# ANYA_2620_V1_I1.net
KiCad netlist of a schematic drawn in Altium Designer
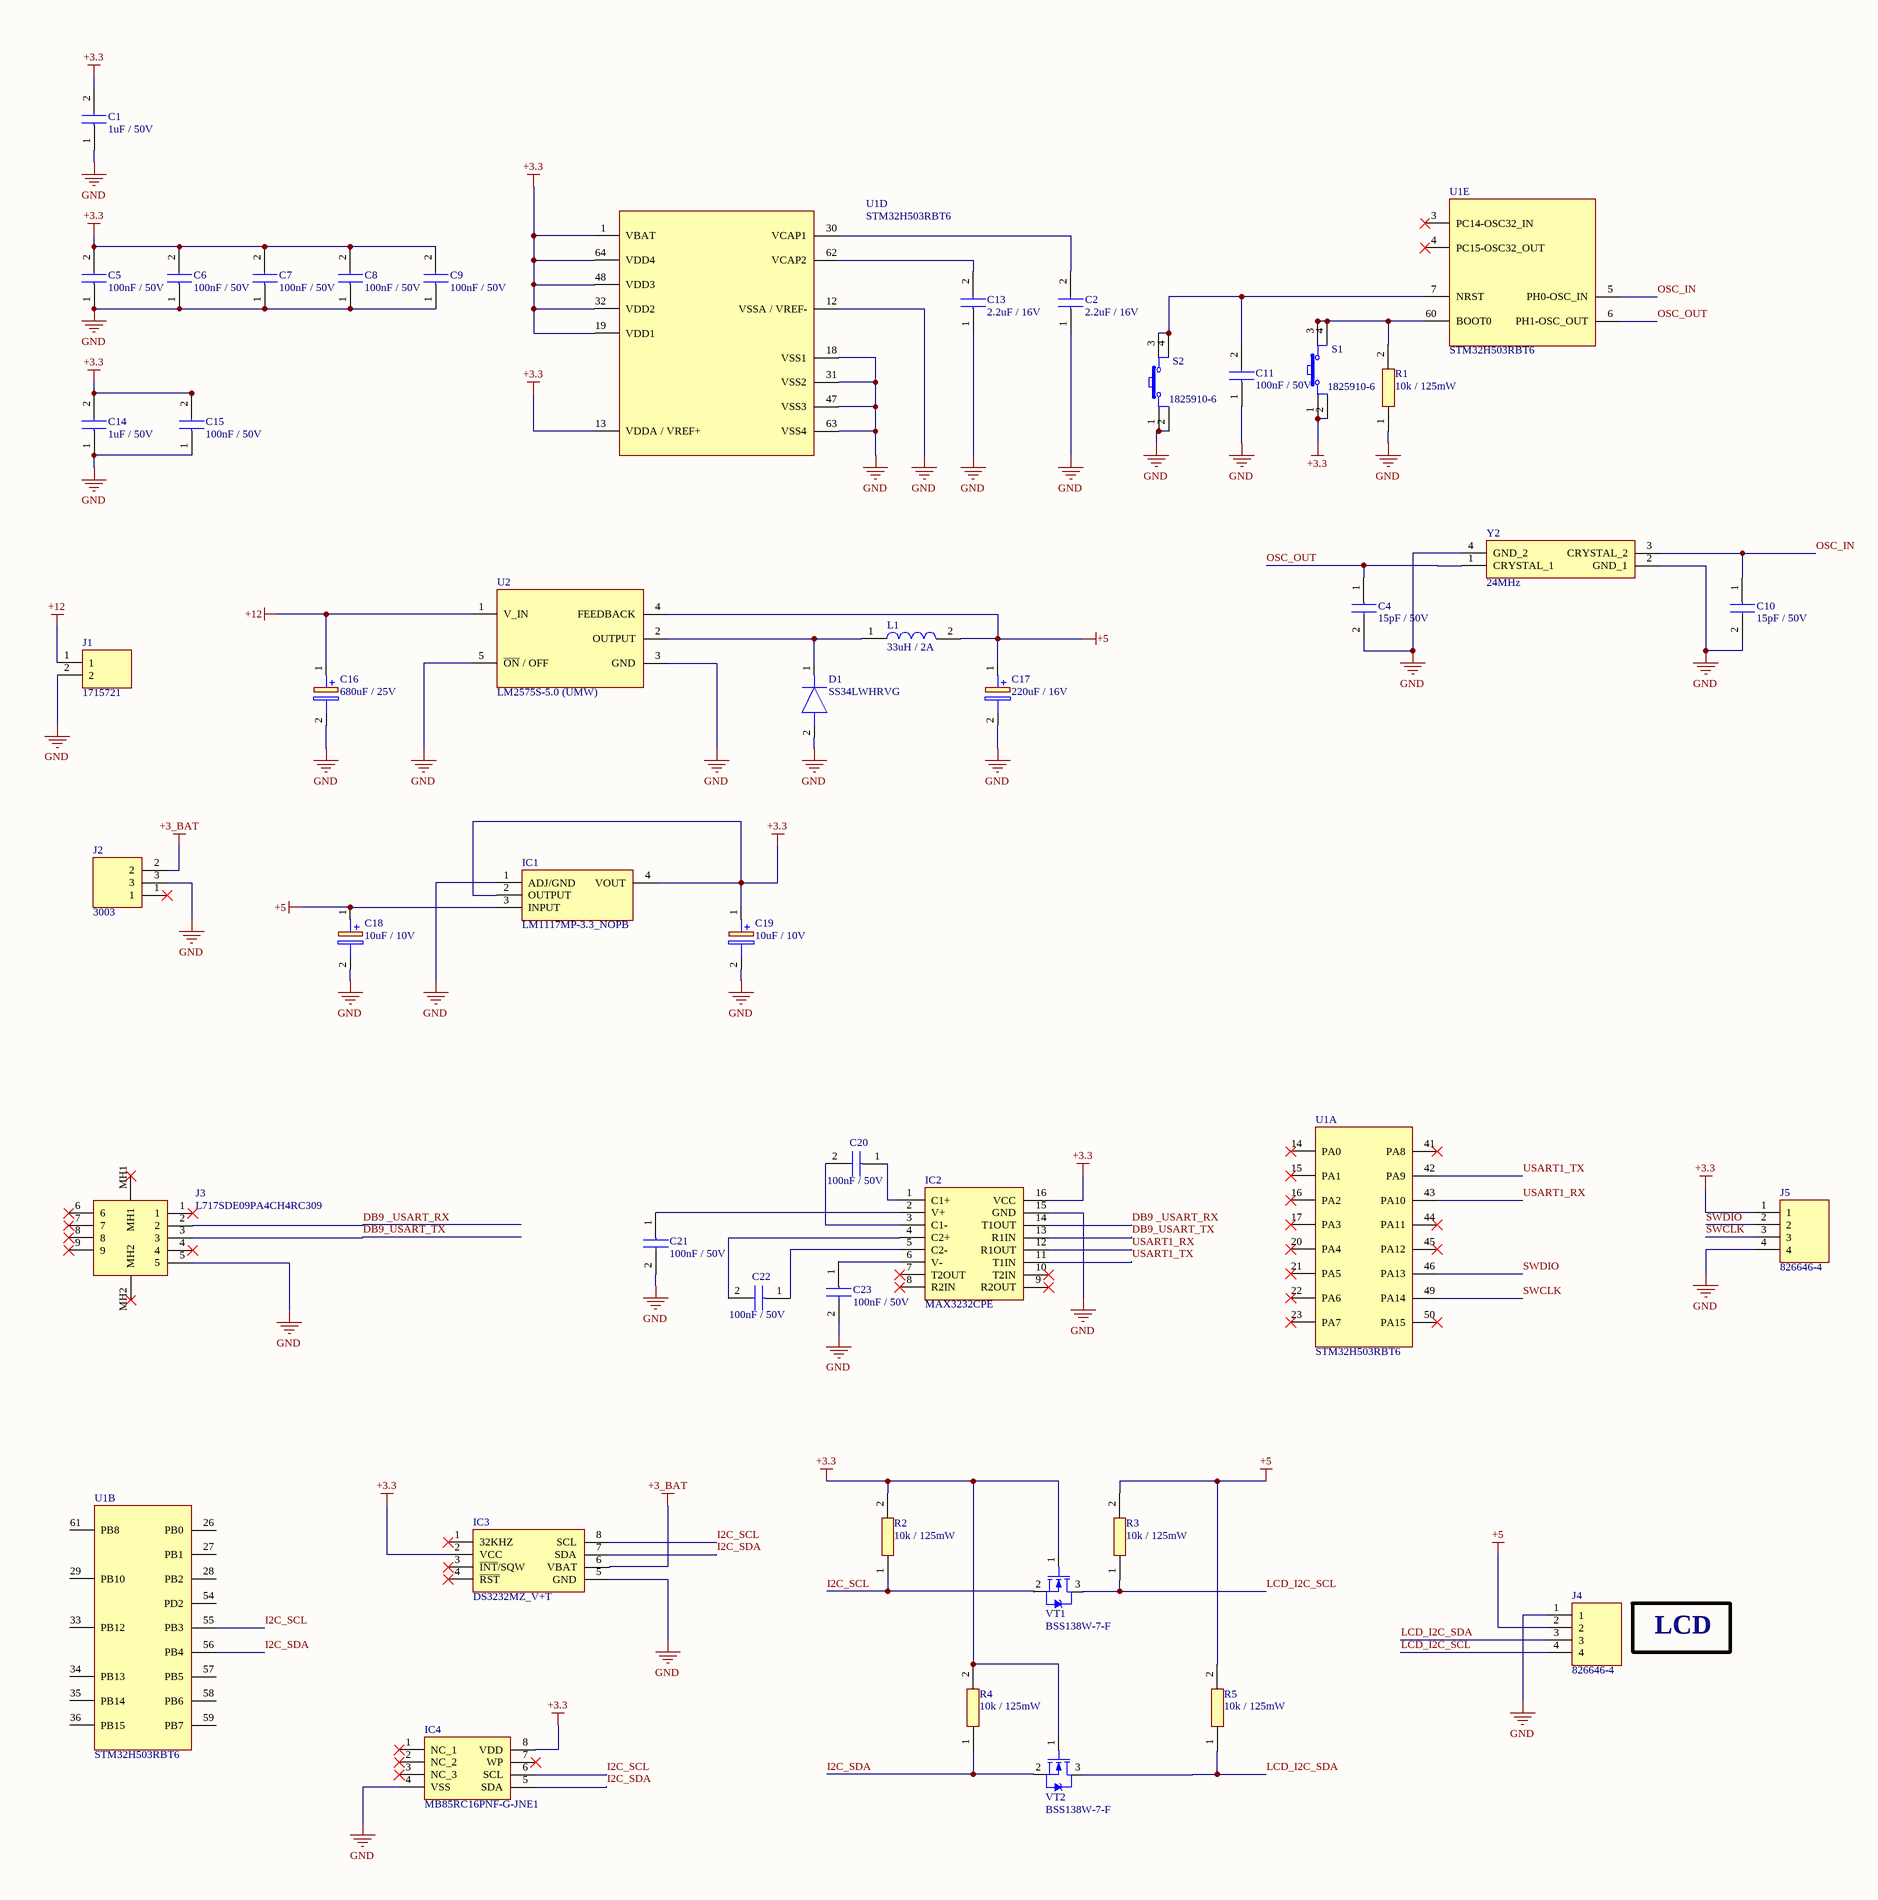
[diagram p0: ANYA_2620_V1_I1.SchDoc, left]
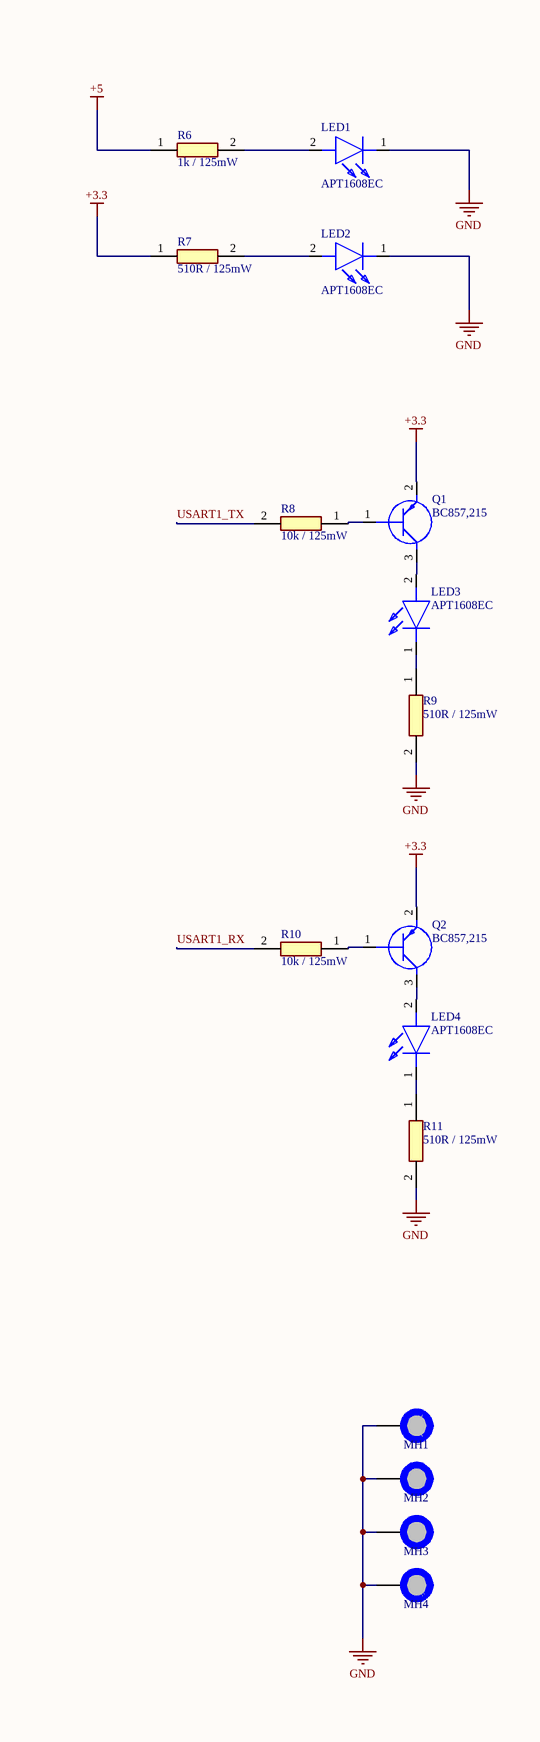
[diagram p1: ANYA_2620_V1_I1.SchDoc, right]

(export (version "E")
  (design (tool "Eeschema 10.0.6"))
  (components
    (comp (ref "C1")
      (value "1uF / 50V")
      (footprint "SamacSys:CAPC2012X145N")
      (description "Capacitor")
      (fields
        (field (name "MANUFACTURER_PART_NUMBER") "GRM21BR71H105KA12L")
        (field (name "MOUSER PART NUMBER") "81-GRM21BR71H105KA2L")
      )
      (libsource (lib "*") (part "GRM21BR71H105KA12L"))
    )
    (comp (ref "C2")
      (value "2.2uF / 16V")
      (footprint "SamacSys:CAPC2012X145N")
      (description "Capacitor")
      (fields
        (field (name "MANUFACTURER_PART_NUMBER") "GRM21BR71C225KA12L")
        (field (name "MOUSER PART NUMBER") "81-GRM21BR71C225KA2L")
      )
      (libsource (lib "*") (part "GRM21BR71C225KA12L"))
    )
    (comp (ref "C4")
      (value "15pF / 50V")
      (footprint "SamacSys:CAPC2012X75N")
      (description "Capacitor")
      (fields (field (name "MANUFACTURER_PART_NUMBER") "CL21C150JBANNNC"))
      (libsource (lib "*") (part "CL21C150JBANNNC"))
    )
    (comp (ref "C5")
      (value "100nF / 50V")
      (footprint "SamacSys:CAPC2012X95N")
      (description "Capacitor")
      (fields
        (field (name "MANUFACTURER_PART_NUMBER") "CL21B104KBCNNNC")
        (field (name "MOUSER PART NUMBER") "187-CL21B104KBCNNNC")
      )
      (libsource (lib "*") (part "CL21B104KBCNNNC"))
    )
    (comp (ref "C6")
      (value "100nF / 50V")
      (footprint "SamacSys:CAPC2012X95N")
      (description "Capacitor")
      (fields
        (field (name "MANUFACTURER_PART_NUMBER") "CL21B104KBCNNNC")
        (field (name "MOUSER PART NUMBER") "187-CL21B104KBCNNNC")
      )
      (libsource (lib "*") (part "CL21B104KBCNNNC"))
    )
    (comp (ref "C7")
      (value "100nF / 50V")
      (footprint "SamacSys:CAPC2012X95N")
      (description "Capacitor")
      (fields
        (field (name "MANUFACTURER_PART_NUMBER") "CL21B104KBCNNNC")
        (field (name "MOUSER PART NUMBER") "187-CL21B104KBCNNNC")
      )
      (libsource (lib "*") (part "CL21B104KBCNNNC"))
    )
    (comp (ref "C8")
      (value "100nF / 50V")
      (footprint "SamacSys:CAPC2012X95N")
      (description "Capacitor")
      (fields
        (field (name "MANUFACTURER_PART_NUMBER") "CL21B104KBCNNNC")
        (field (name "MOUSER PART NUMBER") "187-CL21B104KBCNNNC")
      )
      (libsource (lib "*") (part "CL21B104KBCNNNC"))
    )
    (comp (ref "C9")
      (value "100nF / 50V")
      (footprint "SamacSys:CAPC2012X95N")
      (description "Capacitor")
      (fields
        (field (name "MANUFACTURER_PART_NUMBER") "CL21B104KBCNNNC")
        (field (name "MOUSER PART NUMBER") "187-CL21B104KBCNNNC")
      )
      (libsource (lib "*") (part "CL21B104KBCNNNC"))
    )
    (comp (ref "C10")
      (value "15pF / 50V")
      (footprint "SamacSys:CAPC2012X75N")
      (description "Capacitor")
      (fields (field (name "MANUFACTURER_PART_NUMBER") "CL21C150JBANNNC"))
      (libsource (lib "*") (part "CL21C150JBANNNC"))
    )
    (comp (ref "C11")
      (value "100nF / 50V")
      (footprint "SamacSys:CAPC2012X95N")
      (description "Capacitor")
      (fields
        (field (name "MANUFACTURER_PART_NUMBER") "CL21B104KBCNNNC")
        (field (name "MOUSER PART NUMBER") "187-CL21B104KBCNNNC")
      )
      (libsource (lib "*") (part "CL21B104KBCNNNC"))
    )
    (comp (ref "C13")
      (value "2.2uF / 16V")
      (footprint "SamacSys:CAPC2012X145N")
      (description "Capacitor")
      (fields
        (field (name "MANUFACTURER_PART_NUMBER") "GRM21BR71C225KA12L")
        (field (name "MOUSER PART NUMBER") "81-GRM21BR71C225KA2L")
      )
      (libsource (lib "*") (part "GRM21BR71C225KA12L"))
    )
    (comp (ref "C14")
      (value "1uF / 50V")
      (footprint "SamacSys:CAPC2012X145N")
      (description "Capacitor")
      (fields
        (field (name "MANUFACTURER_PART_NUMBER") "GRM21BR71H105KA12L")
        (field (name "MOUSER PART NUMBER") "81-GRM21BR71H105KA2L")
      )
      (libsource (lib "*") (part "GRM21BR71H105KA12L"))
    )
    (comp (ref "C15")
      (value "100nF / 50V")
      (footprint "SamacSys:CAPC2012X95N")
      (description "Capacitor")
      (fields
        (field (name "MANUFACTURER_PART_NUMBER") "CL21B104KBCNNNC")
        (field (name "MOUSER PART NUMBER") "187-CL21B104KBCNNNC")
      )
      (libsource (lib "*") (part "CL21B104KBCNNNC"))
    )
    (comp (ref "C16")
      (value "680uF / 25V")
      (footprint "SamacSys:CAPPRD500W65D1000H1750")
      (description "Capacitor Polarised")
      (fields
        (field (name "MANUFACTURER_PART_NUMBER") "EEU-FP1E681B")
        (field (name "MOUSER PART NUMBER") "667-EEU-FP1E681B")
      )
      (libsource (lib "*") (part "EEU-FP1E681B"))
    )
    (comp (ref "C17")
      (value "220uF / 16V")
      (footprint "SamacSys:EEEFK0J331AL")
      (description "Capacitor Polarised")
      (fields (field (name "MANUFACTURER_PART_NUMBER") "EEE-FP1C221AL"))
      (libsource (lib "*") (part "EEE-FP1C221AL"))
    )
    (comp (ref "C18")
      (value "10uF / 10V")
      (footprint "SamacSys:T491A")
      (description "Capacitor Polarised")
      (fields
        (field (name "MANUFACTURER_PART_NUMBER") "T491A106K010AT")
        (field (name "MOUSER PART NUMBER") "80-T491A106K010")
      )
      (libsource (lib "*") (part "T491A106K010AT"))
    )
    (comp (ref "C19")
      (value "10uF / 10V")
      (footprint "SamacSys:T491A")
      (description "Capacitor Polarised")
      (fields
        (field (name "MANUFACTURER_PART_NUMBER") "T491A106K010AT")
        (field (name "MOUSER PART NUMBER") "80-T491A106K010")
      )
      (libsource (lib "*") (part "T491A106K010AT"))
    )
    (comp (ref "C20")
      (value "100nF / 50V")
      (footprint "SamacSys:CAPC2012X95N")
      (description "Capacitor")
      (fields
        (field (name "MANUFACTURER_PART_NUMBER") "CL21B104KBCNNNC")
        (field (name "MOUSER PART NUMBER") "187-CL21B104KBCNNNC")
      )
      (libsource (lib "*") (part "CL21B104KBCNNNC"))
    )
    (comp (ref "C21")
      (value "100nF / 50V")
      (footprint "SamacSys:CAPC2012X95N")
      (description "Capacitor")
      (fields
        (field (name "MANUFACTURER_PART_NUMBER") "CL21B104KBCNNNC")
        (field (name "MOUSER PART NUMBER") "187-CL21B104KBCNNNC")
      )
      (libsource (lib "*") (part "CL21B104KBCNNNC"))
    )
    (comp (ref "C22")
      (value "100nF / 50V")
      (footprint "SamacSys:CAPC2012X95N")
      (description "Capacitor")
      (fields
        (field (name "MANUFACTURER_PART_NUMBER") "CL21B104KBCNNNC")
        (field (name "MOUSER PART NUMBER") "187-CL21B104KBCNNNC")
      )
      (libsource (lib "*") (part "CL21B104KBCNNNC"))
    )
    (comp (ref "C23")
      (value "100nF / 50V")
      (footprint "SamacSys:CAPC2012X95N")
      (description "Capacitor")
      (fields
        (field (name "MANUFACTURER_PART_NUMBER") "CL21B104KBCNNNC")
        (field (name "MOUSER PART NUMBER") "187-CL21B104KBCNNNC")
      )
      (libsource (lib "*") (part "CL21B104KBCNNNC"))
    )
    (comp (ref "D1")
      (value "SS34LWHRVG")
      (footprint "SamacSys:SODFL3718X102N")
      (description "Diode")
      (fields (field (name "MOUSER PART NUMBER") "821-SS34LWHRVG"))
      (libsource (lib "*") (part "SS34LWHRVG"))
    )
    (comp (ref "D2") (value "LCD") (footprint "LCD") (libsource (lib "Library") (part "LCD")))
    (comp (ref "IC1")
      (value "LM1117MP-3.3_NOPB")
      (footprint "SamacSys:SOT230P700X180-4N")
      (description "Integrated Circuit")
      (fields
        (field (name "MANUFACTURER_PART_NUMBER") "LM1117MP-3.3/NOPB")
        (field (name "MOUSER PART NUMBER") "926-LM1117MP-3.3NOPB")
      )
      (libsource (lib "*") (part "LM1117MP-3.3_NOPB"))
    )
    (comp (ref "IC2")
      (value "MAX3232CPE")
      (footprint "SamacSys:DIP794W56P254L1918H457Q16N")
      (description "Integrated Circuit")
      (libsource (lib "*") (part "MAX3232CPE"))
    )
    (comp (ref "IC3")
      (value "DS3232MZ_V+T")
      (footprint "SamacSys:SOIC127P600X175-8N")
      (description "Integrated Circuit")
      (fields
        (field (name "MANUFACTURER_PART_NUMBER") "DS3232MZ/V+T")
        (field (name "MOUSER PART NUMBER") "700-DS3232MZ/V+T")
      )
      (libsource (lib "*") (part "DS3232MZ_V+T"))
    )
    (comp (ref "IC4")
      (value "MB85RC16PNF-G-JNE1")
      (footprint "SamacSys:SOIC127P600X175-8N")
      (description "Integrated Circuit")
      (libsource (lib "*") (part "MB85RC16PNF-G-JNE1"))
    )
    (comp (ref "J1")
      (value "1715721")
      (footprint "SamacSys:1715721")
      (description "Connector")
      (fields (field (name "MOUSER PART NUMBER") "651-1715721"))
      (libsource (lib "*") (part "1715721"))
    )
    (comp (ref "J2")
      (value "3003")
      (footprint "SamacSys:3003")
      (description "Connector")
      (fields (field (name "MOUSER PART NUMBER") "534-3003"))
      (libsource (lib "*") (part "3003"))
    )
    (comp (ref "J3")
      (value "L717SDE09PA4CH4RC309")
      (footprint "SamacSys:L717SDE09PA4CH4RC309")
      (description "Connector")
      (fields (field (name "MOUSER PART NUMBER") "523-L7SDE9PA4CH4RC39"))
      (libsource (lib "*") (part "L717SDE09PA4CH4RC309"))
    )
    (comp (ref "J4")
      (value "826646-4")
      (footprint "SamacSys:HDRV4W68P0X254_1X4_1016X250X880P")
      (description "Connector")
      (fields (field (name "MOUSER PART NUMBER") "571-826646-4"))
      (libsource (lib "*") (part "826646-4"))
    )
    (comp (ref "J5")
      (value "826646-4")
      (footprint "SamacSys:HDRV4W68P0X254_1X4_1016X250X880P")
      (description "Connector")
      (fields (field (name "MOUSER PART NUMBER") "571-826646-4"))
      (libsource (lib "*") (part "826646-4"))
    )
    (comp (ref "L1")
      (value "33uH / 2A")
      (footprint "SamacSys:RLB0912330KL")
      (description "Inductor")
      (fields
        (field (name "MANUFACTURER_PART_NUMBER") "RLB0912-330KL")
        (field (name "MOUSER PART NUMBER") "652-RLB0912-330KL")
      )
      (libsource (lib "*") (part "RLB0912-330KL"))
    )
    (comp (ref "LED1")
      (value "APT1608EC")
      (footprint "SamacSys:LEDC1608X85N")
      (description "LED")
      (fields (field (name "MOUSER PART NUMBER") "604-APT1608EC"))
      (libsource (lib "*") (part "APT1608EC"))
    )
    (comp (ref "LED2")
      (value "APT1608EC")
      (footprint "SamacSys:LEDC1608X85N")
      (description "LED")
      (fields (field (name "MOUSER PART NUMBER") "604-APT1608EC"))
      (libsource (lib "*") (part "APT1608EC"))
    )
    (comp (ref "LED3")
      (value "APT1608EC")
      (footprint "SamacSys:LEDC1608X85N")
      (description "LED")
      (fields (field (name "MOUSER PART NUMBER") "604-APT1608EC"))
      (libsource (lib "*") (part "APT1608EC"))
    )
    (comp (ref "LED4")
      (value "APT1608EC")
      (footprint "SamacSys:LEDC1608X85N")
      (description "LED")
      (fields (field (name "MOUSER PART NUMBER") "604-APT1608EC"))
      (libsource (lib "*") (part "APT1608EC"))
    )
    (comp (ref "MH1")
      (value "MH_7.4MMNC_3.2MMD")
      (footprint "MH_7.4MMD_3.2MMD_NON_COPPER_NPTH")
      (description "Mounting Hole 7.4mm Diameter (Non Copper), 3.2mm Drill")
      (libsource (lib "Library") (part "MH_7.4MMNC_3.2MMD"))
    )
    (comp (ref "MH2")
      (value "MH_7.4MMC_3.2MMD")
      (footprint "MH_7.4MMD_3.2MMD")
      (description "Mounting Hole 7.4mm Diameter, 3.2mm Drill")
      (libsource (lib "Library") (part "MH_7.4MMC_3.2MMD"))
    )
    (comp (ref "MH3")
      (value "MH_7.4MMC_3.2MMD")
      (footprint "MH_7.4MMD_3.2MMD")
      (description "Mounting Hole 7.4mm Diameter, 3.2mm Drill")
      (libsource (lib "Library") (part "MH_7.4MMC_3.2MMD"))
    )
    (comp (ref "MH4")
      (value "MH_7.4MMC_3.2MMD")
      (footprint "MH_7.4MMD_3.2MMD")
      (description "Mounting Hole 7.4mm Diameter, 3.2mm Drill")
      (libsource (lib "Library") (part "MH_7.4MMC_3.2MMD"))
    )
    (comp (ref "Q1")
      (value "BC857,215")
      (footprint "SamacSys:BC857215")
      (description "Transistor BJT PNP")
      (fields (field (name "MOUSER PART NUMBER") "771-BC857215"))
      (libsource (lib "*") (part "BC857,215"))
    )
    (comp (ref "Q2")
      (value "BC857,215")
      (footprint "SamacSys:BC857215")
      (description "Transistor BJT PNP")
      (fields (field (name "MOUSER PART NUMBER") "771-BC857215"))
      (libsource (lib "*") (part "BC857,215"))
    )
    (comp (ref "R1")
      (value "10k / 125mW")
      (footprint "SamacSys:RESC2012X60N")
      (description "Resistor")
      (fields
        (field (name "MANUFACTURER_PART_NUMBER") "RC0805FR-0710KL")
        (field (name "MOUSER PART NUMBER") "603-RC0805FR-0710KL")
      )
      (libsource (lib "") (part "RC0805FR-0710KL_1"))
    )
    (comp (ref "R2")
      (value "10k / 125mW")
      (footprint "SamacSys:RESC2012X60N")
      (description "Resistor")
      (fields
        (field (name "MANUFACTURER_PART_NUMBER") "RC0805FR-0710KL")
        (field (name "MOUSER PART NUMBER") "603-RC0805FR-0710KL")
      )
      (libsource (lib "") (part "RC0805FR-0710KL_1"))
    )
    (comp (ref "R3")
      (value "10k / 125mW")
      (footprint "SamacSys:RESC2012X60N")
      (description "Resistor")
      (fields
        (field (name "MANUFACTURER_PART_NUMBER") "RC0805FR-0710KL")
        (field (name "MOUSER PART NUMBER") "603-RC0805FR-0710KL")
      )
      (libsource (lib "") (part "RC0805FR-0710KL_1"))
    )
    (comp (ref "R4")
      (value "10k / 125mW")
      (footprint "SamacSys:RESC2012X60N")
      (description "Resistor")
      (fields
        (field (name "MANUFACTURER_PART_NUMBER") "RC0805FR-0710KL")
        (field (name "MOUSER PART NUMBER") "603-RC0805FR-0710KL")
      )
      (libsource (lib "") (part "RC0805FR-0710KL_1"))
    )
    (comp (ref "R5")
      (value "10k / 125mW")
      (footprint "SamacSys:RESC2012X60N")
      (description "Resistor")
      (fields
        (field (name "MANUFACTURER_PART_NUMBER") "RC0805FR-0710KL")
        (field (name "MOUSER PART NUMBER") "603-RC0805FR-0710KL")
      )
      (libsource (lib "") (part "RC0805FR-0710KL_1"))
    )
    (comp (ref "R6")
      (value "1k / 125mW")
      (footprint "SamacSys:RESC2013X65N")
      (description "Resistor")
      (fields
        (field (name "MANUFACTURER_PART_NUMBER") "0805W8F1001T5E")
        (field (name "MOUSER PART NUMBER") "303-0805W8F1001T5E")
      )
      (libsource (lib "*") (part "0805W8F1001T5E"))
    )
    (comp (ref "R7")
      (value "510R / 125mW")
      (footprint "SamacSys:ERJ6ENF1000V")
      (description "Resistor")
      (fields
        (field (name "MANUFACTURER_PART_NUMBER") "ERJ-6ENF5100V")
        (field (name "MOUSER PART NUMBER") "667-ERJ-6ENF5100V")
      )
      (libsource (lib "") (part "ERJ-6ENF5100V_1"))
    )
    (comp (ref "R8")
      (value "10k / 125mW")
      (footprint "SamacSys:RESC2012X60N")
      (description "Resistor")
      (fields
        (field (name "MANUFACTURER_PART_NUMBER") "RC0805FR-0710KL")
        (field (name "MOUSER PART NUMBER") "603-RC0805FR-0710KL")
      )
      (libsource (lib "*") (part "RC0805FR-0710KL"))
    )
    (comp (ref "R9")
      (value "510R / 125mW")
      (footprint "SamacSys:ERJ6ENF1000V")
      (description "Resistor")
      (fields
        (field (name "MANUFACTURER_PART_NUMBER") "ERJ-6ENF5100V")
        (field (name "MOUSER PART NUMBER") "667-ERJ-6ENF5100V")
      )
      (libsource (lib "*") (part "ERJ-6ENF5100V"))
    )
    (comp (ref "R10")
      (value "10k / 125mW")
      (footprint "SamacSys:RESC2012X60N")
      (description "Resistor")
      (fields
        (field (name "MANUFACTURER_PART_NUMBER") "RC0805FR-0710KL")
        (field (name "MOUSER PART NUMBER") "603-RC0805FR-0710KL")
      )
      (libsource (lib "*") (part "RC0805FR-0710KL"))
    )
    (comp (ref "R11")
      (value "510R / 125mW")
      (footprint "SamacSys:ERJ6ENF1000V")
      (description "Resistor")
      (fields
        (field (name "MANUFACTURER_PART_NUMBER") "ERJ-6ENF5100V")
        (field (name "MOUSER PART NUMBER") "667-ERJ-6ENF5100V")
      )
      (libsource (lib "*") (part "ERJ-6ENF5100V"))
    )
    (comp (ref "S1")
      (value "1825910-6")
      (footprint "TE_1825910-6")
      (description "Switch Tactile OFF (ON) SPST Round Button PC Pins 0.05A 24VDC 1.57N Thru-Hole Loose")
      (fields (field (name "MANUFACTURER") "TE Connectivity"))
      (libsource (lib "Library") (part "1825910-6"))
    )
    (comp (ref "S2")
      (value "1825910-6")
      (footprint "TE_1825910-6")
      (description "Switch Tactile OFF (ON) SPST Round Button PC Pins 0.05A 24VDC 1.57N Thru-Hole Loose")
      (fields (field (name "MANUFACTURER") "TE Connectivity"))
      (libsource (lib "Library") (part "1825910-6"))
    )
    (comp (ref "U1")
      (value "STM32H503RBT6")
      (footprint "QFP64P50_1200X1200X160L60X22N")
      (description "RISC Microcontroller, 32-Bit, FLASH, CORTEX-M4F CPU, 180MHz, CMOS, PBGA216")
      (fields (field (name "MANUFACTURER") "STMicroelectronics"))
      (libsource (lib "") (part "STM32H503RBT6_2"))
    )
    (comp (ref "U2")
      (value "LM2575S-5.0 (UMW)")
      (footprint "DPAK6P170_1534X467L254X81T736X1018N")
      (description "52kHz Buck Fixed 2A 5V TO-263-5 Voltage Regulators - DC DC Switching Regulators RoHS")
      (fields
        (field (name "MANUFACTURER") "UMW")
        (field (name "MANUFACTURER PART NUMBER") "LM2575S-5.0(UMW)")
      )
      (libsource (lib "Library") (part "LM2575S-5.0 (UMW)"))
    )
    (comp (ref "VT1")
      (value "BSS138W-7-F")
      (footprint "SOT23-3P65_222X100L35X30N")
      (description "Transistor: N-MOSFET; unipolar; 50V; 0.2A; 3.5ohm; 0.2W; -55+150 deg.C; SMD; SOT323(SC70)")
      (fields (field (name "MANUFACTURER") "Diodes Inc.") (field (name "VOLTAGE") "50V"))
      (libsource (lib "Library") (part "BSS138W-7-F"))
    )
    (comp (ref "VT2")
      (value "BSS138W-7-F")
      (footprint "SOT23-3P65_222X100L35X30N")
      (description "Transistor: N-MOSFET; unipolar; 50V; 0.2A; 3.5ohm; 0.2W; -55+150 deg.C; SMD; SOT323(SC70)")
      (fields (field (name "MANUFACTURER") "Diodes Inc.") (field (name "VOLTAGE") "50V"))
      (libsource (lib "Library") (part "BSS138W-7-F"))
    )
    (comp (ref "Y2")
      (value "24MHz")
      (footprint "SamacSys:7M24000MEEQT")
      (description "Crystal or Oscillator")
      (fields
        (field (name "MANUFACTURER_PART_NUMBER") "7M-24.000MEEQ-T")
        (field (name "MOUSER PART NUMBER") "717-7M-24.000MEEQ-T")
      )
      (libsource (lib "*") (part "7M-24.000MEEQ-T"))
    )
  )
  (nets
    (net (code "1") (name "+3.3") (class "Default")
      (node (ref "C1") (pin "2") (pinfunction "2_2") (pintype "passive"))
      (node (ref "C14") (pin "2") (pinfunction "2_2") (pintype "passive"))
      (node (ref "C15") (pin "2") (pinfunction "2_2") (pintype "passive"))
      (node (ref "C19") (pin "1") (pinfunction "+_1") (pintype "passive"))
      (node (ref "C5") (pin "2") (pinfunction "2_2") (pintype "passive"))
      (node (ref "C6") (pin "2") (pinfunction "2_2") (pintype "passive"))
      (node (ref "C7") (pin "2") (pinfunction "2_2") (pintype "passive"))
      (node (ref "C8") (pin "2") (pinfunction "2_2") (pintype "passive"))
      (node (ref "C9") (pin "2") (pinfunction "2_2") (pintype "passive"))
      (node (ref "IC1") (pin "2") (pinfunction "OUTPUT_2") (pintype "passive"))
      (node (ref "IC1") (pin "4") (pinfunction "VOUT_4") (pintype "passive"))
      (node (ref "IC2") (pin "16") (pinfunction "VCC_16") (pintype "passive"))
      (node (ref "IC3") (pin "2") (pinfunction "VCC_2") (pintype "passive"))
      (node (ref "IC4") (pin "8") (pinfunction "VDD_8") (pintype "passive"))
      (node (ref "J5") (pin "1") (pinfunction "1_1") (pintype "passive"))
      (node (ref "Q1") (pin "2") (pinfunction "E_2") (pintype "passive"))
      (node (ref "Q2") (pin "2") (pinfunction "E_2") (pintype "passive"))
      (node (ref "R2") (pin "2") (pinfunction "2_2") (pintype "passive"))
      (node (ref "R4") (pin "2") (pinfunction "2_2") (pintype "passive"))
      (node (ref "R7") (pin "1") (pinfunction "1_1") (pintype "passive"))
      (node (ref "S1") (pin "1") (pinfunction "1_1") (pintype "passive"))
      (node (ref "S1") (pin "2") (pinfunction "2_2") (pintype "passive"))
      (node (ref "U1") (pin "1") (pinfunction "VBAT_1") (pintype "passive"))
      (node (ref "U1") (pin "13") (pinfunction "VDDA_/_VREF+_13") (pintype "passive"))
      (node (ref "U1") (pin "19") (pinfunction "VDD1_19") (pintype "passive"))
      (node (ref "U1") (pin "32") (pinfunction "VDD2_32") (pintype "passive"))
      (node (ref "U1") (pin "48") (pinfunction "VDD3_48") (pintype "passive"))
      (node (ref "U1") (pin "64") (pinfunction "VDD4_64") (pintype "passive"))
      (node (ref "VT1") (pin "1") (pinfunction "G_1") (pintype "passive"))
      (node (ref "VT2") (pin "1") (pinfunction "G_1") (pintype "passive"))
    )
    (net (code "2") (name "+3_BAT") (class "Default")
      (node (ref "IC3") (pin "6") (pinfunction "VBAT_6") (pintype "passive"))
      (node (ref "J2") (pin "2") (pinfunction "2_2") (pintype "passive"))
    )
    (net (code "3") (name "+5") (class "Default")
      (node (ref "C17") (pin "1") (pinfunction "+_1") (pintype "passive"))
      (node (ref "C18") (pin "1") (pinfunction "+_1") (pintype "passive"))
      (node (ref "IC1") (pin "3") (pinfunction "INPUT_3") (pintype "passive"))
      (node (ref "J4") (pin "2") (pinfunction "2_2") (pintype "passive"))
      (node (ref "L1") (pin "2") (pinfunction "2_2") (pintype "passive"))
      (node (ref "R3") (pin "2") (pinfunction "2_2") (pintype "passive"))
      (node (ref "R5") (pin "2") (pinfunction "2_2") (pintype "passive"))
      (node (ref "R6") (pin "1") (pinfunction "1_1") (pintype "passive"))
      (node (ref "U2") (pin "4") (pinfunction "FEEDBACK_4") (pintype "passive"))
    )
    (net (code "4") (name "+12") (class "Default")
      (node (ref "C16") (pin "1") (pinfunction "+_1") (pintype "passive"))
      (node (ref "J1") (pin "1") (pinfunction "1_1") (pintype "passive"))
      (node (ref "U2") (pin "1") (pinfunction "V_IN_1") (pintype "passive"))
    )
    (net (code "5") (name "/DB9 _USART_RX") (class "Default")
      (node (ref "IC2") (pin "14") (pinfunction "T1OUT_14") (pintype "passive"))
      (node (ref "J3") (pin "2") (pinfunction "2_2") (pintype "passive"))
    )
    (net (code "6") (name "/DB9_USART_TX") (class "Default")
      (node (ref "IC2") (pin "13") (pinfunction "R1IN_13") (pintype "passive"))
      (node (ref "J3") (pin "3") (pinfunction "3_3") (pintype "passive"))
    )
    (net (code "7") (name "/I2C_SCL") (class "Default")
      (node (ref "IC3") (pin "8") (pinfunction "SCL_8") (pintype "passive"))
      (node (ref "IC4") (pin "6") (pinfunction "SCL_6") (pintype "passive"))
      (node (ref "R2") (pin "1") (pinfunction "1_1") (pintype "passive"))
      (node (ref "U1") (pin "55") (pinfunction "PB3_55") (pintype "passive"))
      (node (ref "VT1") (pin "2") (pinfunction "S_2") (pintype "passive"))
    )
    (net (code "8") (name "/I2C_SDA") (class "Default")
      (node (ref "IC3") (pin "7") (pinfunction "SDA_7") (pintype "passive"))
      (node (ref "IC4") (pin "5") (pinfunction "SDA_5") (pintype "passive"))
      (node (ref "R4") (pin "1") (pinfunction "1_1") (pintype "passive"))
      (node (ref "U1") (pin "56") (pinfunction "PB4_56") (pintype "passive"))
      (node (ref "VT2") (pin "2") (pinfunction "S_2") (pintype "passive"))
    )
    (net (code "9") (name "/LCD_I2C_SCL") (class "Default")
      (node (ref "J4") (pin "4") (pinfunction "4_4") (pintype "passive"))
      (node (ref "R3") (pin "1") (pinfunction "1_1") (pintype "passive"))
      (node (ref "VT1") (pin "3") (pinfunction "D_3") (pintype "passive"))
    )
    (net (code "10") (name "/LCD_I2C_SDA") (class "Default")
      (node (ref "J4") (pin "3") (pinfunction "3_3") (pintype "passive"))
      (node (ref "R5") (pin "1") (pinfunction "1_1") (pintype "passive"))
      (node (ref "VT2") (pin "3") (pinfunction "D_3") (pintype "passive"))
    )
    (net (code "11") (name "/OSC_IN") (class "Default")
      (node (ref "C10") (pin "1") (pinfunction "1_1") (pintype "passive"))
      (node (ref "U1") (pin "5") (pinfunction "PH0-OSC_IN_5") (pintype "passive"))
      (node (ref "Y2") (pin "3") (pinfunction "CRYSTAL_2_3") (pintype "passive"))
    )
    (net (code "12") (name "/OSC_OUT") (class "Default")
      (node (ref "C4") (pin "1") (pinfunction "1_1") (pintype "passive"))
      (node (ref "U1") (pin "6") (pinfunction "PH1-OSC_OUT_6") (pintype "passive"))
      (node (ref "Y2") (pin "1") (pinfunction "CRYSTAL_1_1") (pintype "passive"))
    )
    (net (code "13") (name "/SWCLK") (class "Default")
      (node (ref "J5") (pin "3") (pinfunction "3_3") (pintype "passive"))
      (node (ref "U1") (pin "49") (pinfunction "PA14_49") (pintype "passive"))
    )
    (net (code "14") (name "/SWDIO") (class "Default")
      (node (ref "J5") (pin "2") (pinfunction "2_2") (pintype "passive"))
      (node (ref "U1") (pin "46") (pinfunction "PA13_46") (pintype "passive"))
    )
    (net (code "15") (name "/USART1_RX") (class "Default")
      (node (ref "IC2") (pin "12") (pinfunction "R1OUT_12") (pintype "passive"))
      (node (ref "R10") (pin "2") (pinfunction "2_2") (pintype "passive"))
      (node (ref "U1") (pin "43") (pinfunction "PA10_43") (pintype "passive"))
    )
    (net (code "16") (name "/USART1_TX") (class "Default")
      (node (ref "IC2") (pin "11") (pinfunction "T1IN_11") (pintype "passive"))
      (node (ref "R8") (pin "2") (pinfunction "2_2") (pintype "passive"))
      (node (ref "U1") (pin "42") (pinfunction "PA9_42") (pintype "passive"))
    )
    (net (code "17") (name "GND") (class "Default")
      (node (ref "C1") (pin "1") (pinfunction "1_1") (pintype "passive"))
      (node (ref "C10") (pin "2") (pinfunction "2_2") (pintype "passive"))
      (node (ref "C11") (pin "1") (pinfunction "1_1") (pintype "passive"))
      (node (ref "C13") (pin "1") (pinfunction "1_1") (pintype "passive"))
      (node (ref "C14") (pin "1") (pinfunction "1_1") (pintype "passive"))
      (node (ref "C15") (pin "1") (pinfunction "1_1") (pintype "passive"))
      (node (ref "C16") (pin "2") (pinfunction "-_2") (pintype "passive"))
      (node (ref "C17") (pin "2") (pinfunction "-_2") (pintype "passive"))
      (node (ref "C18") (pin "2") (pinfunction "-_2") (pintype "passive"))
      (node (ref "C19") (pin "2") (pinfunction "-_2") (pintype "passive"))
      (node (ref "C2") (pin "1") (pinfunction "1_1") (pintype "passive"))
      (node (ref "C21") (pin "2") (pinfunction "2_2") (pintype "passive"))
      (node (ref "C23") (pin "2") (pinfunction "2_2") (pintype "passive"))
      (node (ref "C4") (pin "2") (pinfunction "2_2") (pintype "passive"))
      (node (ref "C5") (pin "1") (pinfunction "1_1") (pintype "passive"))
      (node (ref "C6") (pin "1") (pinfunction "1_1") (pintype "passive"))
      (node (ref "C7") (pin "1") (pinfunction "1_1") (pintype "passive"))
      (node (ref "C8") (pin "1") (pinfunction "1_1") (pintype "passive"))
      (node (ref "C9") (pin "1") (pinfunction "1_1") (pintype "passive"))
      (node (ref "D1") (pin "2") (pinfunction "A_2") (pintype "passive"))
      (node (ref "IC1") (pin "1") (pinfunction "ADJ/GND_1") (pintype "passive"))
      (node (ref "IC2") (pin "15") (pinfunction "GND_15") (pintype "passive"))
      (node (ref "IC3") (pin "5") (pinfunction "GND_5") (pintype "passive"))
      (node (ref "IC4") (pin "4") (pinfunction "VSS_4") (pintype "passive"))
      (node (ref "J1") (pin "2") (pinfunction "2_2") (pintype "passive"))
      (node (ref "J2") (pin "3") (pinfunction "3_3") (pintype "passive"))
      (node (ref "J3") (pin "5") (pinfunction "5_5") (pintype "passive"))
      (node (ref "J4") (pin "1") (pinfunction "1_1") (pintype "passive"))
      (node (ref "J5") (pin "4") (pinfunction "4_4") (pintype "passive"))
      (node (ref "LED1") (pin "1") (pinfunction "K_1") (pintype "passive"))
      (node (ref "LED2") (pin "1") (pinfunction "K_1") (pintype "passive"))
      (node (ref "MH1") (pin "1") (pinfunction "1_1") (pintype "passive"))
      (node (ref "MH2") (pin "1") (pinfunction "1_1") (pintype "passive"))
      (node (ref "MH3") (pin "1") (pinfunction "1_1") (pintype "passive"))
      (node (ref "MH4") (pin "1") (pinfunction "1_1") (pintype "passive"))
      (node (ref "R1") (pin "1") (pinfunction "1_1") (pintype "passive"))
      (node (ref "R11") (pin "2") (pinfunction "2_2") (pintype "passive"))
      (node (ref "R9") (pin "2") (pinfunction "2_2") (pintype "passive"))
      (node (ref "S2") (pin "1") (pinfunction "1_1") (pintype "passive"))
      (node (ref "S2") (pin "2") (pinfunction "2_2") (pintype "passive"))
      (node (ref "U1") (pin "12") (pinfunction "VSSA_/_VREF-_12") (pintype "passive"))
      (node (ref "U1") (pin "18") (pinfunction "VSS1_18") (pintype "passive"))
      (node (ref "U1") (pin "31") (pinfunction "VSS2_31") (pintype "passive"))
      (node (ref "U1") (pin "47") (pinfunction "VSS3_47") (pintype "passive"))
      (node (ref "U1") (pin "63") (pinfunction "VSS4_63") (pintype "passive"))
      (node (ref "U2") (pin "3") (pinfunction "GND_3") (pintype "passive"))
      (node (ref "U2") (pin "5") (pinfunction "~{ON}_/_OFF_5") (pintype "passive"))
      (node (ref "Y2") (pin "2") (pinfunction "GND_1_2") (pintype "passive"))
      (node (ref "Y2") (pin "4") (pinfunction "GND_2_4") (pintype "passive"))
    )
    (net (code "18") (name "Net-(D1-K)") (class "Default")
      (node (ref "D1") (pin "1") (pinfunction "K_1") (pintype "passive"))
      (node (ref "L1") (pin "1") (pinfunction "1_1") (pintype "passive"))
      (node (ref "U2") (pin "2") (pinfunction "OUTPUT_2") (pintype "passive"))
    )
    (net (code "19") (name "Net-(IC2-C1+)") (class "Default")
      (node (ref "C20") (pin "1") (pinfunction "1_1") (pintype "passive"))
      (node (ref "IC2") (pin "1") (pinfunction "C1+_1") (pintype "passive"))
    )
    (net (code "20") (name "Net-(IC2-C1-)") (class "Default")
      (node (ref "C20") (pin "2") (pinfunction "2_2") (pintype "passive"))
      (node (ref "IC2") (pin "3") (pinfunction "C1-_3") (pintype "passive"))
    )
    (net (code "21") (name "Net-(IC2-C2+)") (class "Default")
      (node (ref "C22") (pin "2") (pinfunction "2_2") (pintype "passive"))
      (node (ref "IC2") (pin "4") (pinfunction "C2+_4") (pintype "passive"))
    )
    (net (code "22") (name "Net-(IC2-C2-)") (class "Default")
      (node (ref "C22") (pin "1") (pinfunction "1_1") (pintype "passive"))
      (node (ref "IC2") (pin "5") (pinfunction "C2-_5") (pintype "passive"))
    )
    (net (code "23") (name "Net-(IC2-V+)") (class "Default")
      (node (ref "C21") (pin "1") (pinfunction "1_1") (pintype "passive"))
      (node (ref "IC2") (pin "2") (pinfunction "V+_2") (pintype "passive"))
    )
    (net (code "24") (name "Net-(IC2-V-)") (class "Default")
      (node (ref "C23") (pin "1") (pinfunction "1_1") (pintype "passive"))
      (node (ref "IC2") (pin "6") (pinfunction "V-_6") (pintype "passive"))
    )
    (net (code "25") (name "Net-(LED1-A)") (class "Default")
      (node (ref "LED1") (pin "2") (pinfunction "A_2") (pintype "passive"))
      (node (ref "R6") (pin "2") (pinfunction "2_2") (pintype "passive"))
    )
    (net (code "26") (name "Net-(LED2-A)") (class "Default")
      (node (ref "LED2") (pin "2") (pinfunction "A_2") (pintype "passive"))
      (node (ref "R7") (pin "2") (pinfunction "2_2") (pintype "passive"))
    )
    (net (code "27") (name "Net-(LED3-A)") (class "Default")
      (node (ref "LED3") (pin "2") (pinfunction "A_2") (pintype "passive"))
      (node (ref "Q1") (pin "3") (pinfunction "C_3") (pintype "passive"))
    )
    (net (code "28") (name "Net-(LED3-K)") (class "Default")
      (node (ref "LED3") (pin "1") (pinfunction "K_1") (pintype "passive"))
      (node (ref "R9") (pin "1") (pinfunction "1_1") (pintype "passive"))
    )
    (net (code "29") (name "Net-(LED4-A)") (class "Default")
      (node (ref "LED4") (pin "2") (pinfunction "A_2") (pintype "passive"))
      (node (ref "Q2") (pin "3") (pinfunction "C_3") (pintype "passive"))
    )
    (net (code "30") (name "Net-(LED4-K)") (class "Default")
      (node (ref "LED4") (pin "1") (pinfunction "K_1") (pintype "passive"))
      (node (ref "R11") (pin "1") (pinfunction "1_1") (pintype "passive"))
    )
    (net (code "31") (name "Net-(Q1-B)") (class "Default")
      (node (ref "Q1") (pin "1") (pinfunction "B_1") (pintype "passive"))
      (node (ref "R8") (pin "1") (pinfunction "1_1") (pintype "passive"))
    )
    (net (code "32") (name "Net-(Q2-B)") (class "Default")
      (node (ref "Q2") (pin "1") (pinfunction "B_1") (pintype "passive"))
      (node (ref "R10") (pin "1") (pinfunction "1_1") (pintype "passive"))
    )
    (net (code "33") (name "Net-(U1D-VCAP1)") (class "Default")
      (node (ref "C2") (pin "2") (pinfunction "2_2") (pintype "passive"))
      (node (ref "U1") (pin "30") (pinfunction "VCAP1_30") (pintype "passive"))
    )
    (net (code "34") (name "Net-(U1D-VCAP2)") (class "Default")
      (node (ref "C13") (pin "2") (pinfunction "2_2") (pintype "passive"))
      (node (ref "U1") (pin "62") (pinfunction "VCAP2_62") (pintype "passive"))
    )
    (net (code "35") (name "Net-(U1E-BOOT0)") (class "Default")
      (node (ref "R1") (pin "2") (pinfunction "2_2") (pintype "passive"))
      (node (ref "S1") (pin "3") (pinfunction "3_3") (pintype "passive"))
      (node (ref "S1") (pin "4") (pinfunction "4_4") (pintype "passive"))
      (node (ref "U1") (pin "60") (pinfunction "BOOT0_60") (pintype "passive"))
    )
    (net (code "36") (name "Net-(U1E-NRST)") (class "Default")
      (node (ref "C11") (pin "2") (pinfunction "2_2") (pintype "passive"))
      (node (ref "S2") (pin "3") (pinfunction "3_3") (pintype "passive"))
      (node (ref "S2") (pin "4") (pinfunction "4_4") (pintype "passive"))
      (node (ref "U1") (pin "7") (pinfunction "NRST_7") (pintype "passive"))
    )
    (net (code "37") (name "unconnected-(IC2-R2IN-Pad8)") (class "Default")
      (node (ref "IC2") (pin "8") (pinfunction "R2IN_8") (pintype "passive+no_connect"))
    )
    (net (code "38") (name "unconnected-(IC2-R2OUT-Pad9)") (class "Default")
      (node (ref "IC2") (pin "9") (pinfunction "R2OUT_9") (pintype "passive+no_connect"))
    )
    (net (code "39") (name "unconnected-(IC2-T2IN-Pad10)") (class "Default")
      (node (ref "IC2") (pin "10") (pinfunction "T2IN_10") (pintype "passive+no_connect"))
    )
    (net (code "40") (name "unconnected-(IC2-T2OUT-Pad7)") (class "Default")
      (node (ref "IC2") (pin "7") (pinfunction "T2OUT_7") (pintype "passive+no_connect"))
    )
    (net (code "41") (name "unconnected-(IC3-32KHZ-Pad1)") (class "Default")
      (node (ref "IC3") (pin "1") (pinfunction "32KHZ_1") (pintype "passive+no_connect"))
    )
    (net (code "42") (name "unconnected-(IC3-~{INT}{slash}SQW-Pad3)") (class "Default")
      (node (ref "IC3") (pin "3") (pinfunction "~{INT}/SQW_3") (pintype "passive+no_connect"))
    )
    (net (code "43") (name "unconnected-(IC3-~{RST}-Pad4)") (class "Default")
      (node (ref "IC3") (pin "4") (pinfunction "~{RST}_4") (pintype "passive+no_connect"))
    )
    (net (code "44") (name "unconnected-(IC4-NC_1-Pad1)") (class "Default")
      (node (ref "IC4") (pin "1") (pinfunction "NC_1_1") (pintype "passive+no_connect"))
    )
    (net (code "45") (name "unconnected-(IC4-NC_2-Pad2)") (class "Default")
      (node (ref "IC4") (pin "2") (pinfunction "NC_2_2") (pintype "passive+no_connect"))
    )
    (net (code "46") (name "unconnected-(IC4-NC_3-Pad3)") (class "Default")
      (node (ref "IC4") (pin "3") (pinfunction "NC_3_3") (pintype "passive+no_connect"))
    )
    (net (code "47") (name "unconnected-(IC4-WP-Pad7)") (class "Default")
      (node (ref "IC4") (pin "7") (pinfunction "WP_7") (pintype "passive+no_connect"))
    )
    (net (code "48") (name "unconnected-(J2-Pad1)") (class "Default")
      (node (ref "J2") (pin "1") (pinfunction "1_1") (pintype "passive+no_connect"))
    )
    (net (code "49") (name "unconnected-(J3-Pad1)") (class "Default")
      (node (ref "J3") (pin "1") (pinfunction "1_1") (pintype "passive+no_connect"))
    )
    (net (code "50") (name "unconnected-(J3-Pad4)") (class "Default")
      (node (ref "J3") (pin "4") (pinfunction "4_4") (pintype "passive+no_connect"))
    )
    (net (code "51") (name "unconnected-(J3-Pad6)") (class "Default")
      (node (ref "J3") (pin "6") (pinfunction "6_6") (pintype "passive+no_connect"))
    )
    (net (code "52") (name "unconnected-(J3-Pad7)") (class "Default")
      (node (ref "J3") (pin "7") (pinfunction "7_7") (pintype "passive+no_connect"))
    )
    (net (code "53") (name "unconnected-(J3-Pad8)") (class "Default")
      (node (ref "J3") (pin "8") (pinfunction "8_8") (pintype "passive+no_connect"))
    )
    (net (code "54") (name "unconnected-(J3-Pad9)") (class "Default")
      (node (ref "J3") (pin "9") (pinfunction "9_9") (pintype "passive+no_connect"))
    )
    (net (code "55") (name "unconnected-(J3-PadMH1)") (class "Default")
      (node (ref "J3") (pin "MH1") (pinfunction "MH1_MH1") (pintype "passive+no_connect"))
    )
    (net (code "56") (name "unconnected-(J3-PadMH2)") (class "Default")
      (node (ref "J3") (pin "MH2") (pinfunction "MH2_MH2") (pintype "passive+no_connect"))
    )
    (net (code "57") (name "unconnected-(U1A-PA0-Pad14)") (class "Default")
      (node (ref "U1") (pin "14") (pinfunction "PA0_14") (pintype "passive+no_connect"))
    )
    (net (code "58") (name "unconnected-(U1A-PA1-Pad15)") (class "Default")
      (node (ref "U1") (pin "15") (pinfunction "PA1_15") (pintype "passive+no_connect"))
    )
    (net (code "59") (name "unconnected-(U1A-PA2-Pad16)") (class "Default")
      (node (ref "U1") (pin "16") (pinfunction "PA2_16") (pintype "passive+no_connect"))
    )
    (net (code "60") (name "unconnected-(U1A-PA3-Pad17)") (class "Default")
      (node (ref "U1") (pin "17") (pinfunction "PA3_17") (pintype "passive+no_connect"))
    )
    (net (code "61") (name "unconnected-(U1A-PA4-Pad20)") (class "Default")
      (node (ref "U1") (pin "20") (pinfunction "PA4_20") (pintype "passive+no_connect"))
    )
    (net (code "62") (name "unconnected-(U1A-PA5-Pad21)") (class "Default")
      (node (ref "U1") (pin "21") (pinfunction "PA5_21") (pintype "passive+no_connect"))
    )
    (net (code "63") (name "unconnected-(U1A-PA6-Pad22)") (class "Default")
      (node (ref "U1") (pin "22") (pinfunction "PA6_22") (pintype "passive+no_connect"))
    )
    (net (code "64") (name "unconnected-(U1A-PA7-Pad23)") (class "Default")
      (node (ref "U1") (pin "23") (pinfunction "PA7_23") (pintype "passive+no_connect"))
    )
    (net (code "65") (name "unconnected-(U1A-PA8-Pad41)") (class "Default")
      (node (ref "U1") (pin "41") (pinfunction "PA8_41") (pintype "passive+no_connect"))
    )
    (net (code "66") (name "unconnected-(U1A-PA11-Pad44)") (class "Default")
      (node (ref "U1") (pin "44") (pinfunction "PA11_44") (pintype "passive+no_connect"))
    )
    (net (code "67") (name "unconnected-(U1A-PA12-Pad45)") (class "Default")
      (node (ref "U1") (pin "45") (pinfunction "PA12_45") (pintype "passive+no_connect"))
    )
    (net (code "68") (name "unconnected-(U1A-PA15-Pad50)") (class "Default")
      (node (ref "U1") (pin "50") (pinfunction "PA15_50") (pintype "passive+no_connect"))
    )
    (net (code "69") (name "unconnected-(U1B-PB0-Pad26)") (class "Default")
      (node (ref "U1") (pin "26") (pinfunction "PB0_26") (pintype "passive"))
    )
    (net (code "70") (name "unconnected-(U1B-PB1-Pad27)") (class "Default")
      (node (ref "U1") (pin "27") (pinfunction "PB1_27") (pintype "passive"))
    )
    (net (code "71") (name "unconnected-(U1B-PB2-Pad28)") (class "Default")
      (node (ref "U1") (pin "28") (pinfunction "PB2_28") (pintype "passive"))
    )
    (net (code "72") (name "unconnected-(U1B-PB5-Pad57)") (class "Default")
      (node (ref "U1") (pin "57") (pinfunction "PB5_57") (pintype "passive"))
    )
    (net (code "73") (name "unconnected-(U1B-PB6-Pad58)") (class "Default")
      (node (ref "U1") (pin "58") (pinfunction "PB6_58") (pintype "passive"))
    )
    (net (code "74") (name "unconnected-(U1B-PB7-Pad59)") (class "Default")
      (node (ref "U1") (pin "59") (pinfunction "PB7_59") (pintype "passive"))
    )
    (net (code "75") (name "unconnected-(U1B-PB8-Pad61)") (class "Default")
      (node (ref "U1") (pin "61") (pinfunction "PB8_61") (pintype "passive"))
    )
    (net (code "76") (name "unconnected-(U1B-PB10-Pad29)") (class "Default")
      (node (ref "U1") (pin "29") (pinfunction "PB10_29") (pintype "passive"))
    )
    (net (code "77") (name "unconnected-(U1B-PB12-Pad33)") (class "Default")
      (node (ref "U1") (pin "33") (pinfunction "PB12_33") (pintype "passive"))
    )
    (net (code "78") (name "unconnected-(U1B-PB13-Pad34)") (class "Default")
      (node (ref "U1") (pin "34") (pinfunction "PB13_34") (pintype "passive"))
    )
    (net (code "79") (name "unconnected-(U1B-PB14-Pad35)") (class "Default")
      (node (ref "U1") (pin "35") (pinfunction "PB14_35") (pintype "passive"))
    )
    (net (code "80") (name "unconnected-(U1B-PB15-Pad36)") (class "Default")
      (node (ref "U1") (pin "36") (pinfunction "PB15_36") (pintype "passive"))
    )
    (net (code "81") (name "unconnected-(U1B-PD2-Pad54)") (class "Default")
      (node (ref "U1") (pin "54") (pinfunction "PD2_54") (pintype "passive"))
    )
    (net (code "82") (name "unconnected-(U1E-PC14-OSC32_IN-Pad3)") (class "Default")
      (node (ref "U1") (pin "3") (pinfunction "PC14-OSC32_IN_3") (pintype "passive+no_connect"))
    )
    (net (code "83") (name "unconnected-(U1E-PC15-OSC32_OUT-Pad4)") (class "Default")
      (node (ref "U1") (pin "4") (pinfunction "PC15-OSC32_OUT_4") (pintype "passive+no_connect"))
    )
  )
)
